# SQUID_Channel.net
KiCad netlist of a schematic drawn in Altium Designer
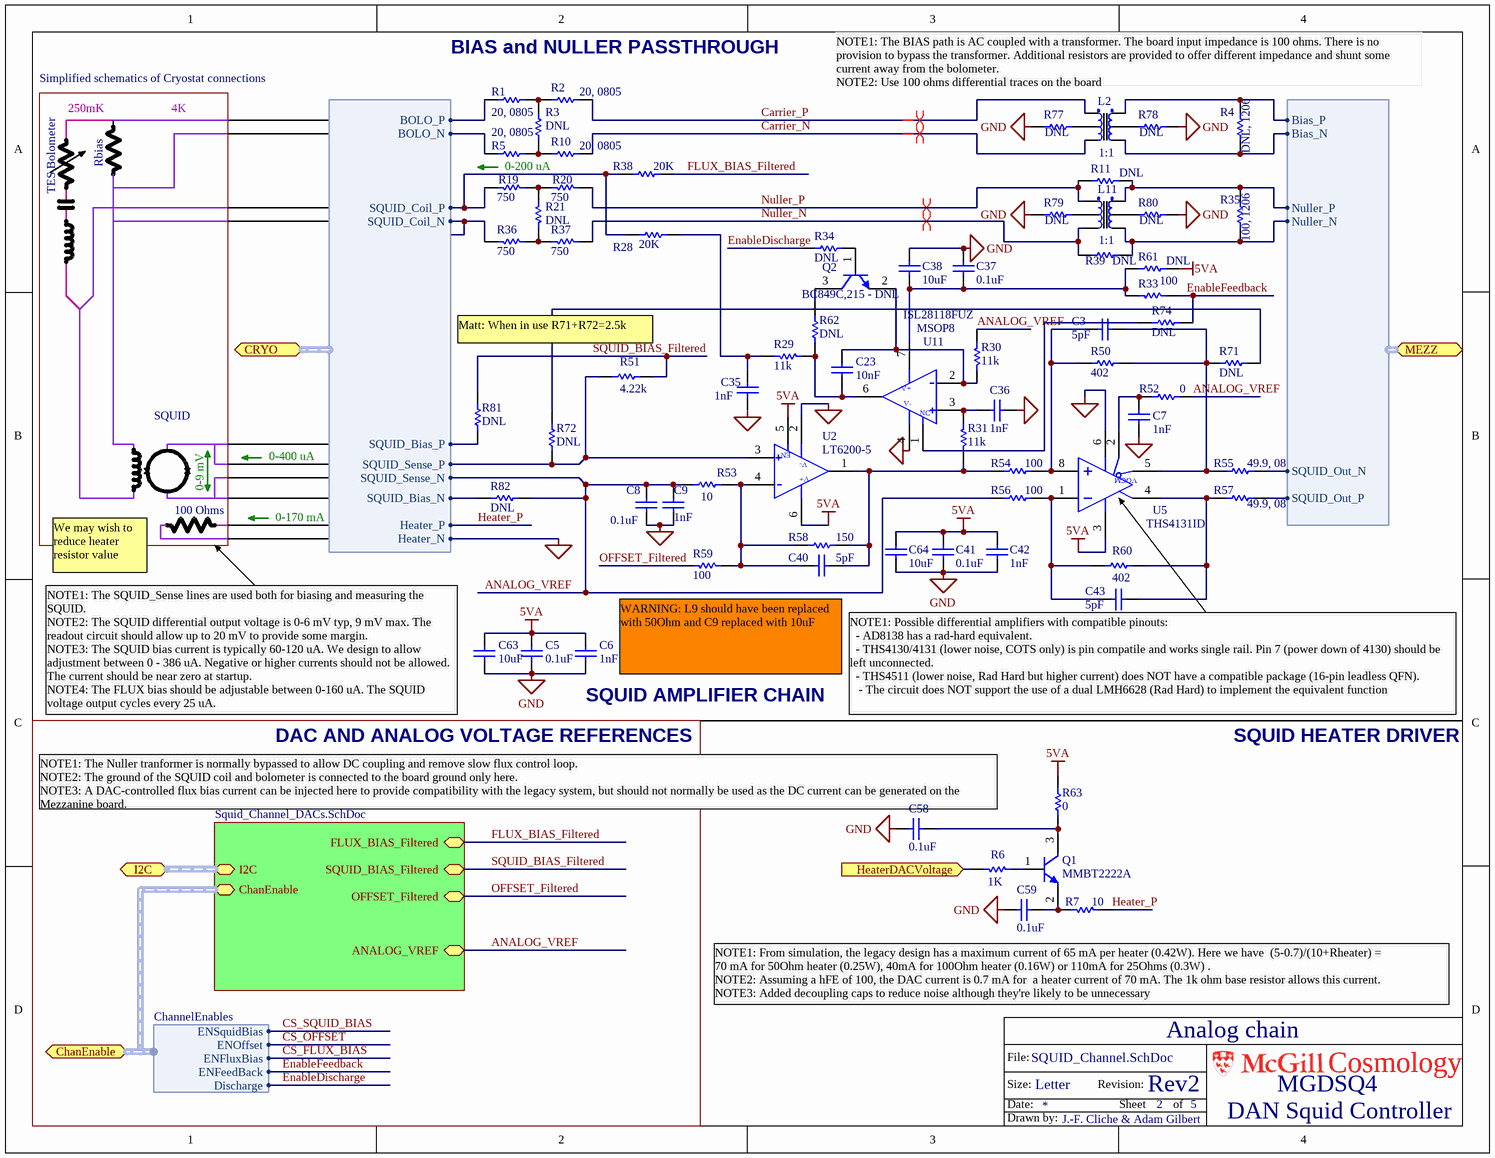
[diagram p0: SQUID_Channel.SchDoc]

(export (version "E")
  (design (tool "Eeschema 10.0.6"))
  (components
    (comp (ref "C3")
      (value "5pF")
      (footprint "0603")
      (description "Capacitor, Ceramic, 0603")
      (fields (field (name "MANUFACTURER") "Generic"))
      (libsource (lib "MiniSquidCtrl") (part "Cap0603"))
    )
    (comp (ref "C5")
      (value "0.1uF")
      (footprint "0603")
      (description "Capacitor, Ceramic, 0603")
      (fields (field (name "MANUFACTURER") "Generic"))
      (libsource (lib "MiniSquidCtrl") (part "Cap0603"))
    )
    (comp (ref "C6")
      (value "1nF")
      (footprint "0603")
      (description "Capacitor, Ceramic, 0603")
      (fields (field (name "MANUFACTURER") "Generic"))
      (libsource (lib "MiniSquidCtrl") (part "Cap0603"))
    )
    (comp (ref "C7")
      (value "1nF")
      (footprint "0603")
      (description "Capacitor, Ceramic, 0603")
      (fields (field (name "MANUFACTURER") "Generic"))
      (libsource (lib "MiniSquidCtrl") (part "Cap0603"))
    )
    (comp (ref "C8")
      (value "0.1uF")
      (footprint "0603")
      (description "Capacitor, Ceramic, 0603")
      (fields (field (name "MANUFACTURER") "Generic"))
      (libsource (lib "MiniSquidCtrl") (part "Cap0603"))
    )
    (comp (ref "C9")
      (value "1nF")
      (footprint "0603")
      (description "Capacitor, Ceramic, 0603")
      (fields (field (name "MANUFACTURER") "Generic"))
      (libsource (lib "MiniSquidCtrl") (part "Cap0603"))
    )
    (comp (ref "C23")
      (value "10nF")
      (footprint "0603")
      (description "Capacitor, Ceramic, 0603")
      (fields (field (name "MANUFACTURER") "Generic") (field (name "TOLERANCE") "±10%"))
      (libsource (lib "MiniSquidCtrl") (part "Cap0603"))
    )
    (comp (ref "C35")
      (value "1nF")
      (footprint "0603")
      (description "Capacitor, Ceramic, 0603")
      (fields (field (name "MANUFACTURER") "Generic"))
      (libsource (lib "MiniSquidCtrl") (part "Cap0603"))
    )
    (comp (ref "C36")
      (value "1nF")
      (footprint "0603")
      (description "Capacitor, Ceramic, 0603")
      (fields (field (name "MANUFACTURER") "Generic"))
      (libsource (lib "MiniSquidCtrl") (part "Cap0603"))
    )
    (comp (ref "C37")
      (value "0.1uF")
      (footprint "0603")
      (description "Capacitor, Ceramic, 0603")
      (fields (field (name "MANUFACTURER") "Generic"))
      (libsource (lib "MiniSquidCtrl") (part "Cap0603"))
    )
    (comp (ref "C38")
      (value "10uF")
      (footprint "CC3225-1210")
      (description "Capacitor, Ceramic, 1210")
      (fields (field (name "MANUFACTURER PART NUMBER") "1206YD106KAT2A") (field (name "VOLTAGE") "16V"))
      (libsource (lib "MiniSquidCtrl") (part "CAP 1210"))
    )
    (comp (ref "C40")
      (value "5pF")
      (footprint "0603")
      (description "Capacitor, Ceramic, 0603")
      (fields (field (name "MANUFACTURER") "Generic"))
      (libsource (lib "MiniSquidCtrl") (part "Cap0603"))
    )
    (comp (ref "C41")
      (value "0.1uF")
      (footprint "0603")
      (description "Capacitor, Ceramic, 0603")
      (fields (field (name "MANUFACTURER") "Generic"))
      (libsource (lib "MiniSquidCtrl") (part "Cap0603"))
    )
    (comp (ref "C42")
      (value "1nF")
      (footprint "0603")
      (description "Capacitor, Ceramic, 0603")
      (fields (field (name "MANUFACTURER") "Generic"))
      (libsource (lib "MiniSquidCtrl") (part "Cap0603"))
    )
    (comp (ref "C43")
      (value "5pF")
      (footprint "0603")
      (description "Capacitor, Ceramic, 0603")
      (fields (field (name "MANUFACTURER") "Generic"))
      (libsource (lib "MiniSquidCtrl") (part "Cap0603"))
    )
    (comp (ref "C58")
      (value "0.1uF")
      (footprint "0603")
      (description "Capacitor, Ceramic, 0603")
      (fields (field (name "MANUFACTURER") "Generic"))
      (libsource (lib "MiniSquidCtrl") (part "Cap0603"))
    )
    (comp (ref "C59")
      (value "0.1uF")
      (footprint "0603")
      (description "Capacitor, Ceramic, 0603")
      (fields (field (name "MANUFACTURER") "Generic"))
      (libsource (lib "MiniSquidCtrl") (part "Cap0603"))
    )
    (comp (ref "C63")
      (value "10uF")
      (footprint "CC3225-1210")
      (description "Capacitor, Ceramic, 1210")
      (fields (field (name "MANUFACTURER PART NUMBER") "1206YD106KAT2A") (field (name "VOLTAGE") "16V"))
      (libsource (lib "MiniSquidCtrl") (part "CAP 1210"))
    )
    (comp (ref "C64")
      (value "10uF")
      (footprint "CC3225-1210")
      (description "Capacitor, Ceramic, 1210")
      (fields (field (name "MANUFACTURER PART NUMBER") "1206YD106KAT2A") (field (name "VOLTAGE") "16V"))
      (libsource (lib "MiniSquidCtrl") (part "CAP 1210"))
    )
    (comp (ref "L2")
      (value "Transformer")
      (footprint "TTWB")
      (fields (field (name "MANUFACTURER") "Coilcraft"))
      (libsource (lib "MiniSquidCtrl") (part "Transformer"))
    )
    (comp (ref "L11")
      (value "Transformer")
      (footprint "TTWB")
      (fields (field (name "MANUFACTURER") "Coilcraft"))
      (libsource (lib "MiniSquidCtrl") (part "Transformer"))
    )
    (comp (ref "Q1")
      (value "MMBT2222A")
      (footprint "SOT23")
      (description "TRANS NPN 40V 350MW SMD SOT23-3")
      (fields (field (name "MANUFACTURER") "Diodes Inc"))
      (libsource (lib "MiniSquidCtrl") (part "2N2222"))
    )
    (comp (ref "Q2")
      (value "BC849C,215 - DNL")
      (footprint "SOT23")
      (description "TRANSISTOR NPN 30V 100MA SOT23")
      (libsource (lib "MiniSquidCtrl") (part "BC849_850"))
    )
    (comp (ref "R1")
      (value "20, 0805")
      (footprint "0805")
      (description "RES 0805 SMD")
      (fields (field (name "MANUFACTURER") "Generic"))
      (libsource (lib "MiniSquidCtrl") (part "RES 0805"))
    )
    (comp (ref "R2")
      (value "20, 0805")
      (footprint "0805")
      (description "RES 0805 SMD")
      (fields (field (name "MANUFACTURER") "Generic"))
      (libsource (lib "MiniSquidCtrl") (part "RES 0805"))
    )
    (comp (ref "R3")
      (value "DNL")
      (footprint "0805")
      (description "RES 0805 SMD")
      (fields (field (name "MANUFACTURER") "Generic"))
      (libsource (lib "MiniSquidCtrl") (part "RES 0805"))
    )
    (comp (ref "R4")
      (value "DNL, 1206")
      (footprint "1206")
      (description "RES 100 OHM 1/4W 1206 SMD")
      (fields
        (field (name "MANUFACTURERS PART NUMBER") "DNL")
        (field (name "MANUFACTURER") "Rohm Semiconductor")
      )
      (libsource (lib "MiniSquidCtrl") (part "RES 1206"))
    )
    (comp (ref "R5")
      (value "20, 0805")
      (footprint "0805")
      (description "RES 0805 SMD")
      (fields (field (name "MANUFACTURER") "Generic"))
      (libsource (lib "MiniSquidCtrl") (part "RES 0805"))
    )
    (comp (ref "R6")
      (value "1K")
      (footprint "0603")
      (description "RES 0603")
      (fields (field (name "MANUFACTURER") "Generic") (field (name "Comment") "1k"))
      (libsource (lib "MiniSquidCtrl") (part "RES 0603"))
    )
    (comp (ref "R7")
      (value "10")
      (footprint "0603")
      (description "RES 0603")
      (fields (field (name "MANUFACTURER") "Generic"))
      (libsource (lib "MiniSquidCtrl") (part "RES 0603"))
    )
    (comp (ref "R10")
      (value "20, 0805")
      (footprint "0805")
      (description "RES 0805 SMD")
      (fields (field (name "MANUFACTURER") "Generic"))
      (libsource (lib "MiniSquidCtrl") (part "RES 0805"))
    )
    (comp (ref "R11")
      (value "DNL")
      (footprint "0603")
      (description "RES 0603")
      (fields (field (name "MANUFACTURER") "Generic"))
      (libsource (lib "MiniSquidCtrl") (part "Res0603"))
    )
    (comp (ref "R19")
      (value "750")
      (footprint "0603")
      (description "RES 0603")
      (fields (field (name "MANUFACTURER") "Generic"))
      (libsource (lib "MiniSquidCtrl") (part "Res0603"))
    )
    (comp (ref "R20")
      (value "750")
      (footprint "0603")
      (description "RES 0603")
      (fields (field (name "MANUFACTURER") "Generic"))
      (libsource (lib "MiniSquidCtrl") (part "Res0603"))
    )
    (comp (ref "R21")
      (value "DNL")
      (footprint "0603")
      (description "RES 0603")
      (fields (field (name "MANUFACTURER") "Generic"))
      (libsource (lib "MiniSquidCtrl") (part "Res0603"))
    )
    (comp (ref "R28")
      (value "20K")
      (footprint "0603")
      (description "RES 0603")
      (fields (field (name "MANUFACTURER") "Generic") (field (name "Comment") "20k"))
      (libsource (lib "MiniSquidCtrl") (part "Res0603"))
    )
    (comp (ref "R29")
      (value "11k")
      (footprint "0603")
      (description "RES 0603")
      (fields (field (name "MANUFACTURER") "Generic"))
      (libsource (lib "MiniSquidCtrl") (part "Res0603"))
    )
    (comp (ref "R30")
      (value "11k")
      (footprint "0603")
      (description "RES 0603")
      (fields (field (name "MANUFACTURER") "Generic"))
      (libsource (lib "MiniSquidCtrl") (part "Res0603"))
    )
    (comp (ref "R31")
      (value "11k")
      (footprint "0603")
      (description "RES 0603")
      (fields (field (name "MANUFACTURER") "Generic"))
      (libsource (lib "MiniSquidCtrl") (part "Res0603"))
    )
    (comp (ref "R33")
      (value "100")
      (footprint "0603")
      (description "RES 0603")
      (fields (field (name "MANUFACTURER") "Generic"))
      (libsource (lib "MiniSquidCtrl") (part "Res0603"))
    )
    (comp (ref "R34")
      (value "DNL")
      (footprint "0603")
      (description "RES 0603")
      (fields (field (name "MANUFACTURER") "Generic"))
      (libsource (lib "MiniSquidCtrl") (part "Res0603"))
    )
    (comp (ref "R35")
      (value "100, 1206")
      (footprint "1206")
      (description "RES 100 OHM 1/4W 1206 SMD")
      (fields
        (field (name "MANUFACTURERS PART NUMBER") "ESR18EZPF1000")
        (field (name "MANUFACTURER") "Rohm Semiconductor")
      )
      (libsource (lib "MiniSquidCtrl") (part "RES 1206"))
    )
    (comp (ref "R36")
      (value "750")
      (footprint "0603")
      (description "RES 0603")
      (fields (field (name "MANUFACTURER") "Generic"))
      (libsource (lib "MiniSquidCtrl") (part "Res0603"))
    )
    (comp (ref "R37")
      (value "750")
      (footprint "0603")
      (description "RES 0603")
      (fields (field (name "MANUFACTURER") "Generic"))
      (libsource (lib "MiniSquidCtrl") (part "Res0603"))
    )
    (comp (ref "R38")
      (value "20K")
      (footprint "0603")
      (description "RES 0603")
      (fields (field (name "MANUFACTURER") "Generic") (field (name "Comment") "20k"))
      (libsource (lib "MiniSquidCtrl") (part "Res0603"))
    )
    (comp (ref "R39")
      (value "DNL")
      (footprint "0603")
      (description "RES 0603")
      (fields (field (name "MANUFACTURER") "Generic"))
      (libsource (lib "MiniSquidCtrl") (part "Res0603"))
    )
    (comp (ref "R48")
      (value "0")
      (footprint "0603")
      (description "RES 0603")
      (fields (field (name "MANUFACTURER") "Generic"))
      (libsource (lib "MiniSquidCtrl") (part "Res0603"))
    )
    (comp (ref "R50")
      (value "402")
      (footprint "0603")
      (description "RES 0603")
      (fields (field (name "MANUFACTURER") "Generic"))
      (libsource (lib "MiniSquidCtrl") (part "RES 0603"))
    )
    (comp (ref "R51")
      (value "4.22k")
      (footprint "0603")
      (description "RES 0603")
      (fields (field (name "MANUFACTURER") "Generic"))
      (libsource (lib "MiniSquidCtrl") (part "Res0603"))
    )
    (comp (ref "R52")
      (value "0")
      (footprint "0603")
      (description "RES 0603")
      (fields (field (name "MANUFACTURER") "Generic"))
      (libsource (lib "MiniSquidCtrl") (part "Res0603"))
    )
    (comp (ref "R53")
      (value "10")
      (footprint "0603")
      (description "RES 0603")
      (fields (field (name "MANUFACTURER") "Generic"))
      (libsource (lib "MiniSquidCtrl") (part "Res0603"))
    )
    (comp (ref "R54")
      (value "100")
      (footprint "0603")
      (description "RES 0603")
      (fields (field (name "MANUFACTURER") "Generic"))
      (libsource (lib "MiniSquidCtrl") (part "Res0603"))
    )
    (comp (ref "R55")
      (value "49.9, 0805")
      (footprint "0805")
      (description "RES 0805 SMD")
      (fields (field (name "MANUFACTURER") "Generic"))
      (libsource (lib "MiniSquidCtrl") (part "RES 0805"))
    )
    (comp (ref "R56")
      (value "100")
      (footprint "0603")
      (description "RES 0603")
      (fields (field (name "MANUFACTURER") "Generic"))
      (libsource (lib "MiniSquidCtrl") (part "Res0603"))
    )
    (comp (ref "R57")
      (value "49.9, 0805")
      (footprint "0805")
      (description "RES 0805 SMD")
      (fields (field (name "MANUFACTURER") "Generic"))
      (libsource (lib "MiniSquidCtrl") (part "RES 0805"))
    )
    (comp (ref "R58")
      (value "150")
      (footprint "0603")
      (description "RES 0603")
      (fields (field (name "MANUFACTURER") "Generic"))
      (libsource (lib "MiniSquidCtrl") (part "Res0603"))
    )
    (comp (ref "R59")
      (value "100")
      (footprint "0603")
      (description "RES 0603")
      (fields (field (name "MANUFACTURER") "Generic"))
      (libsource (lib "MiniSquidCtrl") (part "Res0603"))
    )
    (comp (ref "R60")
      (value "402")
      (footprint "0603")
      (description "RES 0603")
      (fields (field (name "MANUFACTURER") "Generic"))
      (libsource (lib "MiniSquidCtrl") (part "Res0603"))
    )
    (comp (ref "R61")
      (value "DNL")
      (footprint "0603")
      (description "RES 0603")
      (fields (field (name "MANUFACTURER") "Generic"))
      (libsource (lib "MiniSquidCtrl") (part "Res0603"))
    )
    (comp (ref "R62")
      (value "DNL")
      (footprint "0603")
      (description "RES 0603")
      (fields (field (name "MANUFACTURER") "Generic"))
      (libsource (lib "MiniSquidCtrl") (part "Res0603"))
    )
    (comp (ref "R63")
      (value "0")
      (footprint "0603")
      (description "RES 0603")
      (fields (field (name "MANUFACTURER") "Generic"))
      (libsource (lib "MiniSquidCtrl") (part "Res0603"))
    )
    (comp (ref "R71")
      (value "DNL")
      (footprint "0603")
      (description "RES 0603")
      (fields (field (name "MANUFACTURER") "Generic"))
      (libsource (lib "MiniSquidCtrl") (part "Res0603"))
    )
    (comp (ref "R72")
      (value "DNL")
      (footprint "0603")
      (description "RES 0603")
      (fields (field (name "MANUFACTURER") "Generic"))
      (libsource (lib "MiniSquidCtrl") (part "Res0603"))
    )
    (comp (ref "R74")
      (value "DNL")
      (footprint "0603")
      (description "RES 0603")
      (fields (field (name "MANUFACTURER") "Generic"))
      (libsource (lib "MiniSquidCtrl") (part "Res0603"))
    )
    (comp (ref "R77")
      (value "DNL")
      (footprint "0603")
      (description "RES 0603")
      (fields (field (name "MANUFACTURER") "Generic"))
      (libsource (lib "MiniSquidCtrl") (part "Res0603"))
    )
    (comp (ref "R78")
      (value "DNL")
      (footprint "0603")
      (description "RES 0603")
      (fields (field (name "MANUFACTURER") "Generic"))
      (libsource (lib "MiniSquidCtrl") (part "Res0603"))
    )
    (comp (ref "R79")
      (value "DNL")
      (footprint "0603")
      (description "RES 0603")
      (fields (field (name "MANUFACTURER") "Generic"))
      (libsource (lib "MiniSquidCtrl") (part "Res0603"))
    )
    (comp (ref "R80")
      (value "DNL")
      (footprint "0603")
      (description "RES 0603")
      (fields (field (name "MANUFACTURER") "Generic"))
      (libsource (lib "MiniSquidCtrl") (part "Res0603"))
    )
    (comp (ref "R81")
      (value "DNL")
      (footprint "0603")
      (description "RES 0603")
      (fields (field (name "MANUFACTURER") "Generic"))
      (libsource (lib "MiniSquidCtrl") (part "Res0603"))
    )
    (comp (ref "R82")
      (value "DNL")
      (footprint "0603")
      (description "RES 0603")
      (fields (field (name "MANUFACTURER") "Generic"))
      (libsource (lib "MiniSquidCtrl") (part "Res0603"))
    )
    (comp (ref "U2")
      (value "LT6200-5")
      (footprint "SOT23-6")
      (description "IC OPAMP R-R I/O 800MHZ SOT-23-6")
      (libsource (lib "MiniSquidCtrl") (part "LT6200-5"))
    )
    (comp (ref "U5")
      (value "THS4131ID")
      (footprint "SO8")
      (description "IC AMP DIFF LDIST LP 85MA 8SOIC")
      (fields (field (name "MANUFACTURER") "Texas Instruments"))
      (libsource (lib "MiniSquidCtrl") (part "THS4131CD"))
    )
    (comp (ref "U11")
      (value "ISL28118FUZ")
      (footprint "MSOP8-P82B96")
      (description "IC OPAMP PREC R-R 4MHZ LP 8MSOP")
      (libsource (lib "MiniSquidCtrl") (part "ISL28118FUZ"))
    )
  )
  (nets
    (net (code "5") (name "/ANALOG_VREF") (class "Default")
      (node (ref "C8") (pin "2") (pinfunction "2_2") (pintype "passive"))
      (node (ref "C9") (pin "2") (pinfunction "2_2") (pintype "passive"))
      (node (ref "R30") (pin "1") (pinfunction "1_1") (pintype "passive"))
      (node (ref "R52") (pin "1") (pinfunction "1_1") (pintype "passive"))
      (node (ref "R53") (pin "2") (pinfunction "2_2") (pintype "passive"))
      (node (ref "R56") (pin "2") (pinfunction "2_2") (pintype "passive"))
      (node (ref "R82") (pin "2") (pinfunction "2_2") (pintype "passive"))
    )
    (net (code "6") (name "/BOLO_N") (class "Default")
      (node (ref "R5") (pin "1") (pinfunction "1_1") (pintype "passive"))
    )
    (net (code "7") (name "/BOLO_P") (class "Default")
      (node (ref "R1") (pin "1") (pinfunction "1_1") (pintype "passive"))
    )
    (net (code "8") (name "/Bias_N") (class "Default")
      (node (ref "L2") (pin "4") (pinfunction "Sec_4") (pintype "passive"))
      (node (ref "R4") (pin "2") (pinfunction "2_2") (pintype "passive"))
    )
    (net (code "9") (name "/Bias_P") (class "Default")
      (node (ref "L2") (pin "6") (pinfunction "SecDot_6") (pintype "passive"))
      (node (ref "R4") (pin "1") (pinfunction "1_1") (pintype "passive"))
    )
    (net (code "13") (name "/Carrier_N") (class "Default")
      (node (ref "L2") (pin "3") (pinfunction "Prim_3") (pintype "passive"))
      (node (ref "R10") (pin "1") (pinfunction "1_1") (pintype "passive"))
    )
    (net (code "14") (name "/Carrier_P") (class "Default")
      (node (ref "L2") (pin "1") (pinfunction "PrimDot_1") (pintype "passive"))
      (node (ref "R2") (pin "1") (pinfunction "1_1") (pintype "passive"))
    )
    (net (code "15") (name "/EnableDischarge") (class "Default")
      (node (ref "R34") (pin "1") (pinfunction "1_1") (pintype "passive"))
    )
    (net (code "16") (name "/EnableFeedback") (class "Default")
      (node (ref "R33") (pin "2") (pinfunction "2_2") (pintype "passive"))
      (node (ref "R74") (pin "1") (pinfunction "1_1") (pintype "passive"))
    )
    (net (code "17") (name "/FLUX_BIAS_Filtered") (class "Default")
      (node (ref "R38") (pin "1") (pinfunction "1_1") (pintype "passive"))
    )
    (net (code "18") (name "/HeaterDACVoltage") (class "Default")
      (node (ref "R6") (pin "2") (pinfunction "2_2") (pintype "passive"))
    )
    (net (code "19") (name "/Heater_P") (class "Default")
      (node (ref "R7") (pin "1") (pinfunction "1_1") (pintype "passive"))
    )
    (net (code "21") (name "/Nuller_N") (class "Default")
      (node (ref "L11") (pin "3") (pinfunction "Prim_3") (pintype "passive"))
      (node (ref "R37") (pin "2") (pinfunction "2_2") (pintype "passive"))
      (node (ref "R39") (pin "1") (pinfunction "1_1") (pintype "passive"))
    )
    (net (code "22") (name "/Nuller_P") (class "Default")
      (node (ref "L11") (pin "1") (pinfunction "PrimDot_1") (pintype "passive"))
      (node (ref "R11") (pin "1") (pinfunction "1_1") (pintype "passive"))
      (node (ref "R20") (pin "2") (pinfunction "2_2") (pintype "passive"))
    )
    (net (code "23") (name "/OFFSET_Filtered") (class "Default")
      (node (ref "R59") (pin "1") (pinfunction "1_1") (pintype "passive"))
    )
    (net (code "24") (name "/SQUID_BIAS_Filtered") (class "Default")
      (node (ref "R51") (pin "1") (pinfunction "1_1") (pintype "passive"))
      (node (ref "R81") (pin "1") (pinfunction "1_1") (pintype "passive"))
    )
    (net (code "25") (name "/SQUID_Bias_N") (class "Default")
      (node (ref "R82") (pin "1") (pinfunction "1_1") (pintype "passive"))
    )
    (net (code "26") (name "/SQUID_Bias_P") (class "Default")
      (node (ref "R81") (pin "2") (pinfunction "2_2") (pintype "passive"))
    )
    (net (code "27") (name "/SQUID_Coil_N") (class "Default")
      (node (ref "R36") (pin "2") (pinfunction "2_2") (pintype "passive"))
      (node (ref "R48") (pin "1") (pinfunction "1_1") (pintype "passive"))
    )
    (net (code "28") (name "/SQUID_Coil_P") (class "Default")
      (node (ref "R19") (pin "2") (pinfunction "2_2") (pintype "passive"))
      (node (ref "R28") (pin "1") (pinfunction "1_1") (pintype "passive"))
      (node (ref "R38") (pin "2") (pinfunction "2_2") (pintype "passive"))
    )
    (net (code "29") (name "/SQUID_Out_N") (class "Default")
      (node (ref "R55") (pin "2") (pinfunction "2_2") (pintype "passive"))
    )
    (net (code "30") (name "/SQUID_Out_P") (class "Default")
      (node (ref "R57") (pin "2") (pinfunction "2_2") (pintype "passive"))
    )
    (net (code "31") (name "/SQUID_Sense_P") (class "Default")
      (node (ref "R51") (pin "2") (pinfunction "2_2") (pintype "passive"))
      (node (ref "R72") (pin "2") (pinfunction "2_2") (pintype "passive"))
      (node (ref "U2") (pin "3") (pinfunction "IN+_3") (pintype "passive"))
    )
    (net (code "35") (name "5VA") (class "Default")
      (node (ref "C41") (pin "2") (pinfunction "2_2") (pintype "passive"))
      (node (ref "C42") (pin "2") (pinfunction "2_2") (pintype "passive"))
      (node (ref "C5") (pin "2") (pinfunction "2_2") (pintype "passive"))
      (node (ref "C6") (pin "2") (pinfunction "2_2") (pintype "passive"))
      (node (ref "C63") (pin "2") (pinfunction "2_2") (pintype "passive"))
      (node (ref "C64") (pin "2") (pinfunction "2_2") (pintype "passive"))
      (node (ref "R61") (pin "2") (pinfunction "2_2") (pintype "passive"))
      (node (ref "R63") (pin "1") (pinfunction "1_1") (pintype "passive"))
      (node (ref "U2") (pin "5") (pinfunction "En_5") (pintype "passive"))
      (node (ref "U2") (pin "6") (pinfunction "V+_6") (pintype "power_in"))
      (node (ref "U5") (pin "3") (pinfunction "V+_3") (pintype "power_in"))
    )
    (net (code "36") (name "GND") (class "Default")
      (node (ref "C35") (pin "2") (pinfunction "2_2") (pintype "passive"))
      (node (ref "C36") (pin "1") (pinfunction "1_1") (pintype "passive"))
      (node (ref "C37") (pin "1") (pinfunction "1_1") (pintype "passive"))
      (node (ref "C38") (pin "1") (pinfunction "1_1") (pintype "passive"))
      (node (ref "C41") (pin "1") (pinfunction "1_1") (pintype "passive"))
      (node (ref "C42") (pin "1") (pinfunction "1_1") (pintype "passive"))
      (node (ref "C5") (pin "1") (pinfunction "1_1") (pintype "passive"))
      (node (ref "C58") (pin "2") (pinfunction "2_2") (pintype "passive"))
      (node (ref "C59") (pin "2") (pinfunction "2_2") (pintype "passive"))
      (node (ref "C6") (pin "1") (pinfunction "1_1") (pintype "passive"))
      (node (ref "C63") (pin "1") (pinfunction "1_1") (pintype "passive"))
      (node (ref "C64") (pin "1") (pinfunction "1_1") (pintype "passive"))
      (node (ref "C7") (pin "1") (pinfunction "1_1") (pintype "passive"))
      (node (ref "C8") (pin "1") (pinfunction "1_1") (pintype "passive"))
      (node (ref "C9") (pin "1") (pinfunction "1_1") (pintype "passive"))
      (node (ref "R48") (pin "2") (pinfunction "2_2") (pintype "passive"))
      (node (ref "R77") (pin "1") (pinfunction "1_1") (pintype "passive"))
      (node (ref "R78") (pin "2") (pinfunction "2_2") (pintype "passive"))
      (node (ref "R79") (pin "1") (pinfunction "1_1") (pintype "passive"))
      (node (ref "R80") (pin "2") (pinfunction "2_2") (pintype "passive"))
      (node (ref "U11") (pin "4") (pinfunction "V-_4") (pintype "power_in"))
      (node (ref "U2") (pin "2") (pinfunction "V-_2") (pintype "power_in"))
      (node (ref "U5") (pin "6") (pinfunction "V-_6") (pintype "power_in"))
    )
    (net (code "37") (name "Net-(C35-Pad1)") (class "Default")
      (node (ref "C35") (pin "1") (pinfunction "1_1") (pintype "passive"))
      (node (ref "R28") (pin "2") (pinfunction "2_2") (pintype "passive"))
      (node (ref "R29") (pin "1") (pinfunction "1_1") (pintype "passive"))
    )
    (net (code "38") (name "Net-(L2-PrimCent)") (class "Default")
      (node (ref "L2") (pin "2") (pinfunction "PrimCent_2") (pintype "passive"))
      (node (ref "R77") (pin "2") (pinfunction "2_2") (pintype "passive"))
    )
    (net (code "39") (name "Net-(L2-SecCent)") (class "Default")
      (node (ref "L2") (pin "5") (pinfunction "SecCent_5") (pintype "passive"))
      (node (ref "R78") (pin "1") (pinfunction "1_1") (pintype "passive"))
    )
    (net (code "40") (name "Net-(L11-PrimCent)") (class "Default")
      (node (ref "L11") (pin "2") (pinfunction "PrimCent_2") (pintype "passive"))
      (node (ref "R79") (pin "2") (pinfunction "2_2") (pintype "passive"))
    )
    (net (code "41") (name "Net-(L11-Sec)") (class "Default")
      (node (ref "L11") (pin "4") (pinfunction "Sec_4") (pintype "passive"))
      (node (ref "R35") (pin "2") (pinfunction "2_2") (pintype "passive"))
      (node (ref "R39") (pin "2") (pinfunction "2_2") (pintype "passive"))
    )
    (net (code "42") (name "Net-(L11-SecCent)") (class "Default")
      (node (ref "L11") (pin "5") (pinfunction "SecCent_5") (pintype "passive"))
      (node (ref "R80") (pin "1") (pinfunction "1_1") (pintype "passive"))
    )
    (net (code "43") (name "Net-(L11-SecDot)") (class "Default")
      (node (ref "L11") (pin "6") (pinfunction "SecDot_6") (pintype "passive"))
      (node (ref "R11") (pin "2") (pinfunction "2_2") (pintype "passive"))
      (node (ref "R35") (pin "1") (pinfunction "1_1") (pintype "passive"))
    )
    (net (code "44") (name "Net-(Q1-B)") (class "Default")
      (node (ref "Q1") (pin "1") (pinfunction "B_1") (pintype "passive"))
      (node (ref "R6") (pin "1") (pinfunction "1_1") (pintype "passive"))
    )
    (net (code "45") (name "Net-(Q1-C)") (class "Default")
      (node (ref "C58") (pin "1") (pinfunction "1_1") (pintype "passive"))
      (node (ref "Q1") (pin "3") (pinfunction "C_3") (pintype "passive"))
      (node (ref "R63") (pin "2") (pinfunction "2_2") (pintype "passive"))
    )
    (net (code "46") (name "Net-(Q1-E)") (class "Default")
      (node (ref "C59") (pin "1") (pinfunction "1_1") (pintype "passive"))
      (node (ref "Q1") (pin "2") (pinfunction "E_2") (pintype "passive"))
      (node (ref "R7") (pin "2") (pinfunction "2_2") (pintype "passive"))
    )
    (net (code "47") (name "Net-(Q2-B)") (class "Default")
      (node (ref "Q2") (pin "1") (pinfunction "B_1") (pintype "passive"))
      (node (ref "R34") (pin "2") (pinfunction "2_2") (pintype "passive"))
    )
    (net (code "48") (name "Net-(Q2-C)") (class "Default")
      (node (ref "Q2") (pin "3") (pinfunction "C_3") (pintype "passive"))
      (node (ref "R62") (pin "2") (pinfunction "2_2") (pintype "passive"))
    )
    (net (code "49") (name "Net-(Q2-E)") (class "Default")
      (node (ref "C23") (pin "1") (pinfunction "1_1") (pintype "passive"))
      (node (ref "Q2") (pin "2") (pinfunction "E_2") (pintype "passive"))
      (node (ref "R30") (pin "2") (pinfunction "2_2") (pintype "passive"))
      (node (ref "U11") (pin "2") (pinfunction "IN-_2") (pintype "passive"))
    )
    (net (code "50") (name "Net-(R1-Pad2)") (class "Default")
      (node (ref "R1") (pin "2") (pinfunction "2_2") (pintype "passive"))
      (node (ref "R2") (pin "2") (pinfunction "2_2") (pintype "passive"))
      (node (ref "R3") (pin "1") (pinfunction "1_1") (pintype "passive"))
    )
    (net (code "51") (name "Net-(R10-Pad2)") (class "Default")
      (node (ref "R10") (pin "2") (pinfunction "2_2") (pintype "passive"))
      (node (ref "R3") (pin "2") (pinfunction "2_2") (pintype "passive"))
      (node (ref "R5") (pin "2") (pinfunction "2_2") (pintype "passive"))
    )
    (net (code "52") (name "Net-(R19-Pad1)") (class "Default")
      (node (ref "R19") (pin "1") (pinfunction "1_1") (pintype "passive"))
      (node (ref "R20") (pin "1") (pinfunction "1_1") (pintype "passive"))
      (node (ref "R21") (pin "1") (pinfunction "1_1") (pintype "passive"))
    )
    (net (code "53") (name "Net-(R21-Pad2)") (class "Default")
      (node (ref "R21") (pin "2") (pinfunction "2_2") (pintype "passive"))
      (node (ref "R36") (pin "1") (pinfunction "1_1") (pintype "passive"))
      (node (ref "R37") (pin "1") (pinfunction "1_1") (pintype "passive"))
    )
    (net (code "54") (name "Net-(R71-Pad2)") (class "Default")
      (node (ref "R71") (pin "2") (pinfunction "2_2") (pintype "passive"))
      (node (ref "R72") (pin "1") (pinfunction "1_1") (pintype "passive"))
    )
    (net (code "55") (name "Net-(U2-IN-)") (class "Default")
      (node (ref "C40") (pin "2") (pinfunction "2_2") (pintype "passive"))
      (node (ref "R53") (pin "1") (pinfunction "1_1") (pintype "passive"))
      (node (ref "R58") (pin "2") (pinfunction "2_2") (pintype "passive"))
      (node (ref "R59") (pin "2") (pinfunction "2_2") (pintype "passive"))
      (node (ref "U2") (pin "4") (pinfunction "IN-_4") (pintype "passive"))
    )
    (net (code "56") (name "Net-(U2-OUT)") (class "Default")
      (node (ref "C40") (pin "1") (pinfunction "1_1") (pintype "passive"))
      (node (ref "R31") (pin "1") (pinfunction "1_1") (pintype "passive"))
      (node (ref "R54") (pin "2") (pinfunction "2_2") (pintype "passive"))
      (node (ref "R58") (pin "1") (pinfunction "1_1") (pintype "passive"))
      (node (ref "U2") (pin "1") (pinfunction "OUT_1") (pintype "passive"))
    )
    (net (code "57") (name "Net-(U5-IN+)") (class "Default")
      (node (ref "C3") (pin "2") (pinfunction "2_2") (pintype "passive"))
      (node (ref "R50") (pin "2") (pinfunction "2_2") (pintype "passive"))
      (node (ref "R54") (pin "1") (pinfunction "1_1") (pintype "passive"))
      (node (ref "U5") (pin "8") (pinfunction "IN+_8") (pintype "passive"))
    )
    (net (code "58") (name "Net-(U5-IN-)") (class "Default")
      (node (ref "C43") (pin "2") (pinfunction "2_2") (pintype "passive"))
      (node (ref "R56") (pin "1") (pinfunction "1_1") (pintype "passive"))
      (node (ref "R60") (pin "2") (pinfunction "2_2") (pintype "passive"))
      (node (ref "U5") (pin "1") (pinfunction "IN-_1") (pintype "passive"))
    )
    (net (code "59") (name "Net-(U5-OUT+)") (class "Default")
      (node (ref "C43") (pin "1") (pinfunction "1_1") (pintype "passive"))
      (node (ref "R57") (pin "1") (pinfunction "1_1") (pintype "passive"))
      (node (ref "R60") (pin "1") (pinfunction "1_1") (pintype "passive"))
      (node (ref "U5") (pin "4") (pinfunction "OUT+_4") (pintype "passive"))
    )
    (net (code "60") (name "Net-(U5-OUT-)") (class "Default")
      (node (ref "C3") (pin "1") (pinfunction "1_1") (pintype "passive"))
      (node (ref "R50") (pin "1") (pinfunction "1_1") (pintype "passive"))
      (node (ref "R55") (pin "1") (pinfunction "1_1") (pintype "passive"))
      (node (ref "R71") (pin "1") (pinfunction "1_1") (pintype "passive"))
      (node (ref "U5") (pin "5") (pinfunction "OUT-_5") (pintype "passive"))
    )
    (net (code "61") (name "Net-(U5-VOCM)") (class "Default")
      (node (ref "C7") (pin "2") (pinfunction "2_2") (pintype "passive"))
      (node (ref "R52") (pin "2") (pinfunction "2_2") (pintype "passive"))
      (node (ref "U5") (pin "2") (pinfunction "VOCM_2") (pintype "passive"))
    )
    (net (code "62") (name "Net-(U11-IN+)") (class "Default")
      (node (ref "C36") (pin "2") (pinfunction "2_2") (pintype "passive"))
      (node (ref "R31") (pin "2") (pinfunction "2_2") (pintype "passive"))
      (node (ref "U11") (pin "3") (pinfunction "IN+_3") (pintype "passive"))
    )
    (net (code "63") (name "Net-(U11-OUT-)") (class "Default")
      (node (ref "C23") (pin "2") (pinfunction "2_2") (pintype "passive"))
      (node (ref "R29") (pin "2") (pinfunction "2_2") (pintype "passive"))
      (node (ref "R62") (pin "1") (pinfunction "1_1") (pintype "passive"))
      (node (ref "U11") (pin "6") (pinfunction "OUT-_6") (pintype "passive"))
    )
    (net (code "64") (name "Net-(U11-SHDN)") (class "Default")
      (node (ref "R74") (pin "2") (pinfunction "2_2") (pintype "passive"))
      (node (ref "U11") (pin "1") (pinfunction "SHDN_1") (pintype "passive"))
    )
    (net (code "65") (name "Net-(U11-V+)") (class "Default")
      (node (ref "C37") (pin "2") (pinfunction "2_2") (pintype "passive"))
      (node (ref "C38") (pin "2") (pinfunction "2_2") (pintype "passive"))
      (node (ref "R33") (pin "1") (pinfunction "1_1") (pintype "passive"))
      (node (ref "R61") (pin "1") (pinfunction "1_1") (pintype "passive"))
      (node (ref "U11") (pin "7") (pinfunction "V+_7") (pintype "power_in"))
    )
    (net (code "66") (name "unconnected-(U5-NC-Pad7)") (class "Default")
      (node (ref "U5") (pin "7") (pinfunction "NC_7") (pintype "passive"))
    )
  )
)
